# battery_charger.net
KiCad netlist of a schematic drawn in EAGLE
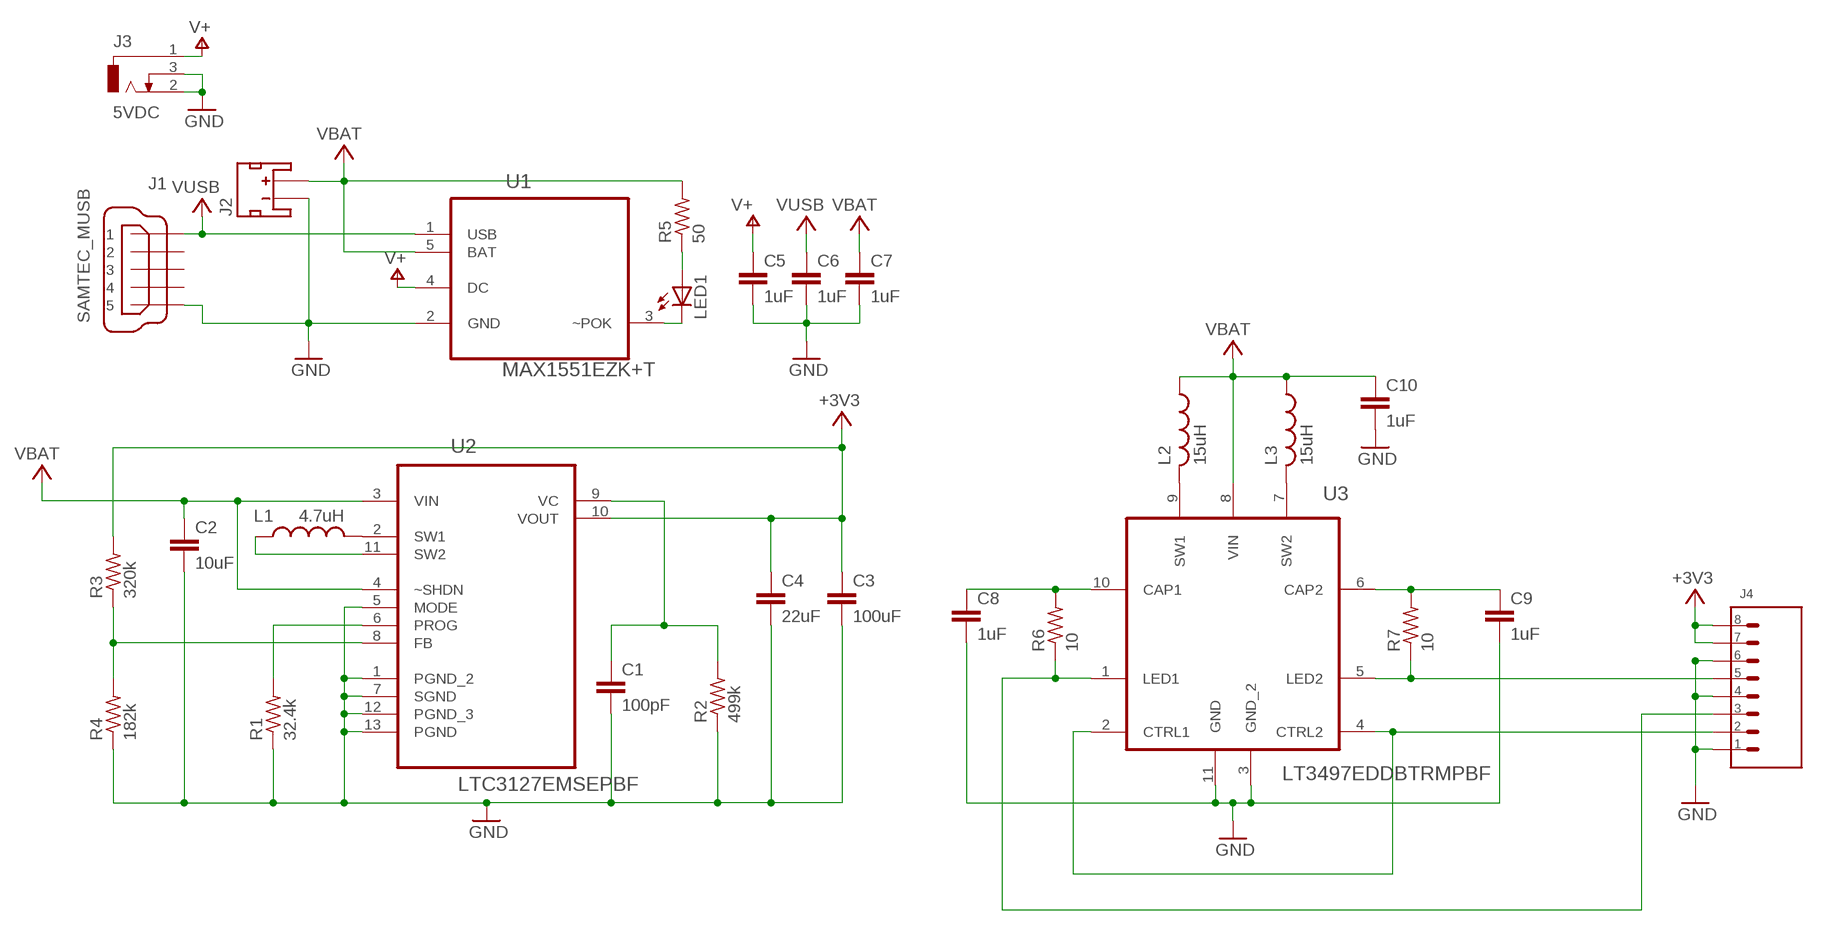
[diagram p0: schematic, sheet 1]

(export (version "E")
  (design (tool "Eeschema 10.0.6"))
  (components
    (comp (ref "C1")
      (value "100pF")
      (footprint "eagle-import:C0402")
      (libsource (lib "eagle-import") (part "C-EUC0402"))
    )
    (comp (ref "C2")
      (value "10uF")
      (footprint "eagle-import:C0402")
      (libsource (lib "eagle-import") (part "C-EUC0402"))
    )
    (comp (ref "C3")
      (value "100uF")
      (footprint "eagle-import:C1206")
      (libsource (lib "eagle-import") (part "C-EUC1206"))
    )
    (comp (ref "C4")
      (value "22uF")
      (footprint "eagle-import:C0805")
      (libsource (lib "eagle-import") (part "C-EUC0805"))
    )
    (comp (ref "C5")
      (value "1uF")
      (footprint "eagle-import:C0402")
      (libsource (lib "eagle-import") (part "C-EUC0402"))
    )
    (comp (ref "C6")
      (value "1uF")
      (footprint "eagle-import:C0402")
      (libsource (lib "eagle-import") (part "C-EUC0402"))
    )
    (comp (ref "C7")
      (value "1uF")
      (footprint "eagle-import:C0402")
      (libsource (lib "eagle-import") (part "C-EUC0402"))
    )
    (comp (ref "C8")
      (value "1uF")
      (footprint "eagle-import:C0805")
      (libsource (lib "eagle-import") (part "C-EUC0805"))
    )
    (comp (ref "C9")
      (value "1uF")
      (footprint "eagle-import:C0805")
      (libsource (lib "eagle-import") (part "C-EUC0805"))
    )
    (comp (ref "C10")
      (value "1uF")
      (footprint "eagle-import:C0402")
      (libsource (lib "eagle-import") (part "C-EUC0402"))
    )
    (comp (ref "J1")
      (value "SAMTEC_MUSB")
      (footprint "eagle-import:MUSB-05-X-B-SM-A")
      (libsource (lib "eagle-import") (part "SAMTEC_MUSB"))
    )
    (comp (ref "J2")
      (value "JST_2MM_SMT")
      (footprint "eagle-import:JST_2MM_SMT")
      (libsource (lib "eagle-import") (part "JST_2MM_SMT"))
    )
    (comp (ref "J3")
      (value "5VDC")
      (footprint "eagle-import:PJ-045")
      (libsource (lib "eagle-import") (part "DC_POWER_JACK_PJ-045"))
    )
    (comp (ref "J4")
      (value "IO")
      (footprint "eagle-import:8-PIN_SIP_.100IN")
      (libsource (lib "eagle-import") (part "8PIN_SIP_.100IN"))
    )
    (comp (ref "L1")
      (value "4.7uH")
      (footprint "eagle-import:NR6028")
      (libsource (lib "eagle-import") (part "INDUCTOR_NR6028"))
    )
    (comp (ref "L2")
      (value "15uH")
      (footprint "eagle-import:L3225M")
      (libsource (lib "eagle-import") (part "L-USL3225M"))
    )
    (comp (ref "L3")
      (value "15uH")
      (footprint "eagle-import:L3225M")
      (libsource (lib "eagle-import") (part "L-USL3225M"))
    )
    (comp (ref "LED1")
      (value "CHG")
      (footprint "eagle-import:CHIPLED_0603")
      (libsource (lib "eagle-import") (part "LEDCHIPLED_0603"))
    )
    (comp (ref "R1")
      (value "32.4k")
      (footprint "eagle-import:R0402")
      (libsource (lib "eagle-import") (part "R-US_R0402"))
    )
    (comp (ref "R2")
      (value "499k")
      (footprint "eagle-import:R0402")
      (libsource (lib "eagle-import") (part "R-US_R0402"))
    )
    (comp (ref "R3")
      (value "320k")
      (footprint "eagle-import:R0402")
      (libsource (lib "eagle-import") (part "R-US_R0402"))
    )
    (comp (ref "R4")
      (value "182k")
      (footprint "eagle-import:R0402")
      (libsource (lib "eagle-import") (part "R-US_R0402"))
    )
    (comp (ref "R5")
      (value "50")
      (footprint "eagle-import:R0402")
      (libsource (lib "eagle-import") (part "R-US_R0402"))
    )
    (comp (ref "R6")
      (value "10")
      (footprint "eagle-import:R0402")
      (libsource (lib "eagle-import") (part "R-US_R0402"))
    )
    (comp (ref "R7")
      (value "10")
      (footprint "eagle-import:R0402")
      (libsource (lib "eagle-import") (part "R-US_R0402"))
    )
    (comp (ref "U1")
      (value "MAX1551EZK+T")
      (footprint "eagle-import:SOT95P275X110-5N")
      (libsource (lib "eagle-import") (part "MAX1551EZK+T"))
    )
    (comp (ref "U2")
      (value "LTC3127EMSEPBF")
      (footprint "eagle-import:SOP65P490X110-13N")
      (fields (field (name "MANUFACTURER") "LTC3127EMSE#PBF"))
      (libsource (lib "eagle-import") (part "LTC3127EMSEPBF"))
    )
    (comp (ref "U3")
      (value "LT3497EDDBTRMPBF")
      (footprint "eagle-import:DFN300X200X80-11N")
      (fields (field (name "MPN") "LT3497EDDB#TRMPBF"))
      (libsource (lib "eagle-import") (part "LT3497EDDBTRMPBF"))
    )
  )
  (nets
    (net (code "1") (name "+3V3") (class "Default")
      (node (ref "C3") (pin "1") (pinfunction "1_1") (pintype "passive"))
      (node (ref "C4") (pin "1") (pinfunction "1_1") (pintype "passive"))
      (node (ref "J4") (pin "7") (pinfunction "S7_7") (pintype "passive"))
      (node (ref "J4") (pin "8") (pinfunction "S8_8") (pintype "passive"))
      (node (ref "R3") (pin "2") (pinfunction "2_2") (pintype "passive"))
      (node (ref "U2") (pin "10") (pinfunction "VOUT_10") (pintype "output"))
    )
    (net (code "2") (name "GND") (class "Default")
      (node (ref "C1") (pin "2") (pinfunction "2_2") (pintype "passive"))
      (node (ref "C10") (pin "2") (pinfunction "2_2") (pintype "passive"))
      (node (ref "C2") (pin "2") (pinfunction "2_2") (pintype "passive"))
      (node (ref "C3") (pin "2") (pinfunction "2_2") (pintype "passive"))
      (node (ref "C4") (pin "2") (pinfunction "2_2") (pintype "passive"))
      (node (ref "C5") (pin "2") (pinfunction "2_2") (pintype "passive"))
      (node (ref "C6") (pin "2") (pinfunction "2_2") (pintype "passive"))
      (node (ref "C7") (pin "2") (pinfunction "2_2") (pintype "passive"))
      (node (ref "C8") (pin "2") (pinfunction "2_2") (pintype "passive"))
      (node (ref "C9") (pin "2") (pinfunction "2_2") (pintype "passive"))
      (node (ref "J1") (pin "5") (pinfunction "5_5") (pintype "input"))
      (node (ref "J2") (pin "1") (pinfunction "-_1") (pintype "bidirectional"))
      (node (ref "J3") (pin "2") (pinfunction "2_2") (pintype "passive"))
      (node (ref "J3") (pin "3") (pinfunction "3_3") (pintype "passive"))
      (node (ref "J4") (pin "1") (pinfunction "S1_1") (pintype "passive"))
      (node (ref "J4") (pin "4") (pinfunction "S4_4") (pintype "passive"))
      (node (ref "J4") (pin "6") (pinfunction "S6_6") (pintype "passive"))
      (node (ref "R1") (pin "1") (pinfunction "1_1") (pintype "passive"))
      (node (ref "R2") (pin "1") (pinfunction "1_1") (pintype "passive"))
      (node (ref "R4") (pin "1") (pinfunction "1_1") (pintype "passive"))
      (node (ref "U1") (pin "2") (pinfunction "GND_2") (pintype "passive"))
      (node (ref "U2") (pin "1") (pinfunction "PGND_2_1") (pintype "passive"))
      (node (ref "U2") (pin "12") (pinfunction "PGND_3_12") (pintype "passive"))
      (node (ref "U2") (pin "13") (pinfunction "PGND_13") (pintype "passive"))
      (node (ref "U2") (pin "5") (pinfunction "MODE_5") (pintype "input"))
      (node (ref "U2") (pin "7") (pinfunction "SGND_7") (pintype "passive"))
      (node (ref "U3") (pin "11") (pinfunction "GND_11") (pintype "passive"))
      (node (ref "U3") (pin "3") (pinfunction "GND_2_3") (pintype "passive"))
    )
    (net (code "3") (name "Net-(J4-S2)") (class "Default")
      (node (ref "J4") (pin "2") (pinfunction "S2_2") (pintype "passive"))
      (node (ref "U3") (pin "2") (pinfunction "CTRL1_2") (pintype "input"))
      (node (ref "U3") (pin "4") (pinfunction "CTRL2_4") (pintype "input"))
    )
    (net (code "4") (name "Net-(J4-S3)") (class "Default")
      (node (ref "J4") (pin "3") (pinfunction "S3_3") (pintype "passive"))
      (node (ref "R6") (pin "1") (pinfunction "1_1") (pintype "passive"))
      (node (ref "U3") (pin "1") (pinfunction "LED1_1") (pintype "output"))
    )
    (net (code "5") (name "Net-(J4-S5)") (class "Default")
      (node (ref "J4") (pin "5") (pinfunction "S5_5") (pintype "passive"))
      (node (ref "R7") (pin "1") (pinfunction "1_1") (pintype "passive"))
      (node (ref "U3") (pin "5") (pinfunction "LED2_5") (pintype "output"))
    )
    (net (code "6") (name "Net-(LED1-PadA)") (class "Default")
      (node (ref "LED1") (pin "A") (pinfunction "A_A") (pintype "passive"))
      (node (ref "R5") (pin "1") (pinfunction "1_1") (pintype "passive"))
    )
    (net (code "7") (name "Net-(U1-~{POK})") (class "Default")
      (node (ref "LED1") (pin "C") (pinfunction "C_C") (pintype "passive"))
      (node (ref "U1") (pin "3") (pinfunction "~{POK}_3") (pintype "passive"))
    )
    (net (code "8") (name "Net-(U2-FB)") (class "Default")
      (node (ref "R3") (pin "1") (pinfunction "1_1") (pintype "passive"))
      (node (ref "R4") (pin "2") (pinfunction "2_2") (pintype "passive"))
      (node (ref "U2") (pin "8") (pinfunction "FB_8") (pintype "input"))
    )
    (net (code "9") (name "Net-(U2-PROG)") (class "Default")
      (node (ref "R1") (pin "2") (pinfunction "2_2") (pintype "passive"))
      (node (ref "U2") (pin "6") (pinfunction "PROG_6") (pintype "input"))
    )
    (net (code "10") (name "Net-(U2-SW1)") (class "Default")
      (node (ref "L1") (pin "2") (pinfunction "2_2") (pintype "passive"))
      (node (ref "U2") (pin "2") (pinfunction "SW1_2") (pintype "passive"))
    )
    (net (code "11") (name "Net-(U2-SW2)") (class "Default")
      (node (ref "L1") (pin "1") (pinfunction "1_1") (pintype "passive"))
      (node (ref "U2") (pin "11") (pinfunction "SW2_11") (pintype "passive"))
    )
    (net (code "12") (name "Net-(U2-VC)") (class "Default")
      (node (ref "C1") (pin "1") (pinfunction "1_1") (pintype "passive"))
      (node (ref "R2") (pin "2") (pinfunction "2_2") (pintype "passive"))
      (node (ref "U2") (pin "9") (pinfunction "VC_9") (pintype "output"))
    )
    (net (code "13") (name "Net-(U3-CAP1)") (class "Default")
      (node (ref "C8") (pin "1") (pinfunction "1_1") (pintype "passive"))
      (node (ref "R6") (pin "2") (pinfunction "2_2") (pintype "passive"))
      (node (ref "U3") (pin "10") (pinfunction "CAP1_10") (pintype "output"))
    )
    (net (code "14") (name "Net-(U3-CAP2)") (class "Default")
      (node (ref "C9") (pin "1") (pinfunction "1_1") (pintype "passive"))
      (node (ref "R7") (pin "2") (pinfunction "2_2") (pintype "passive"))
      (node (ref "U3") (pin "6") (pinfunction "CAP2_6") (pintype "input"))
    )
    (net (code "15") (name "Net-(U3-SW1)") (class "Default")
      (node (ref "L2") (pin "2") (pinfunction "2_2") (pintype "passive"))
      (node (ref "U3") (pin "9") (pinfunction "SW1_9") (pintype "passive"))
    )
    (net (code "16") (name "Net-(U3-SW2)") (class "Default")
      (node (ref "L3") (pin "2") (pinfunction "2_2") (pintype "passive"))
      (node (ref "U3") (pin "7") (pinfunction "SW2_7") (pintype "passive"))
    )
    (net (code "17") (name "V+") (class "Default")
      (node (ref "C5") (pin "1") (pinfunction "1_1") (pintype "passive"))
      (node (ref "J3") (pin "1") (pinfunction "1_1") (pintype "passive"))
      (node (ref "U1") (pin "4") (pinfunction "DC_4") (pintype "passive"))
    )
    (net (code "18") (name "VBAT") (class "Default")
      (node (ref "C10") (pin "1") (pinfunction "1_1") (pintype "passive"))
      (node (ref "C2") (pin "1") (pinfunction "1_1") (pintype "passive"))
      (node (ref "C7") (pin "1") (pinfunction "1_1") (pintype "passive"))
      (node (ref "J2") (pin "2") (pinfunction "+_2") (pintype "bidirectional"))
      (node (ref "L2") (pin "1") (pinfunction "1_1") (pintype "passive"))
      (node (ref "L3") (pin "1") (pinfunction "1_1") (pintype "passive"))
      (node (ref "R5") (pin "2") (pinfunction "2_2") (pintype "passive"))
      (node (ref "U1") (pin "5") (pinfunction "BAT_5") (pintype "power_in"))
      (node (ref "U2") (pin "3") (pinfunction "VIN_3") (pintype "power_in"))
      (node (ref "U2") (pin "4") (pinfunction "~{SHDN}_4") (pintype "input"))
      (node (ref "U3") (pin "8") (pinfunction "VIN_8") (pintype "power_in"))
    )
    (net (code "19") (name "VUSB") (class "Default")
      (node (ref "C6") (pin "1") (pinfunction "1_1") (pintype "passive"))
      (node (ref "J1") (pin "1") (pinfunction "1_1") (pintype "input"))
      (node (ref "U1") (pin "1") (pinfunction "USB_1") (pintype "power_in"))
    )
    (net (code "20") (name "unconnected-(J1-Pad2)") (class "Default")
      (node (ref "J1") (pin "2") (pinfunction "2_2") (pintype "input"))
    )
    (net (code "21") (name "unconnected-(J1-Pad3)") (class "Default")
      (node (ref "J1") (pin "3") (pinfunction "3_3") (pintype "input"))
    )
    (net (code "22") (name "unconnected-(J1-Pad4)") (class "Default")
      (node (ref "J1") (pin "4") (pinfunction "4_4") (pintype "input"))
    )
  )
)
